# atmega328_dip_board.net
KiCad netlist of a schematic drawn in EAGLE
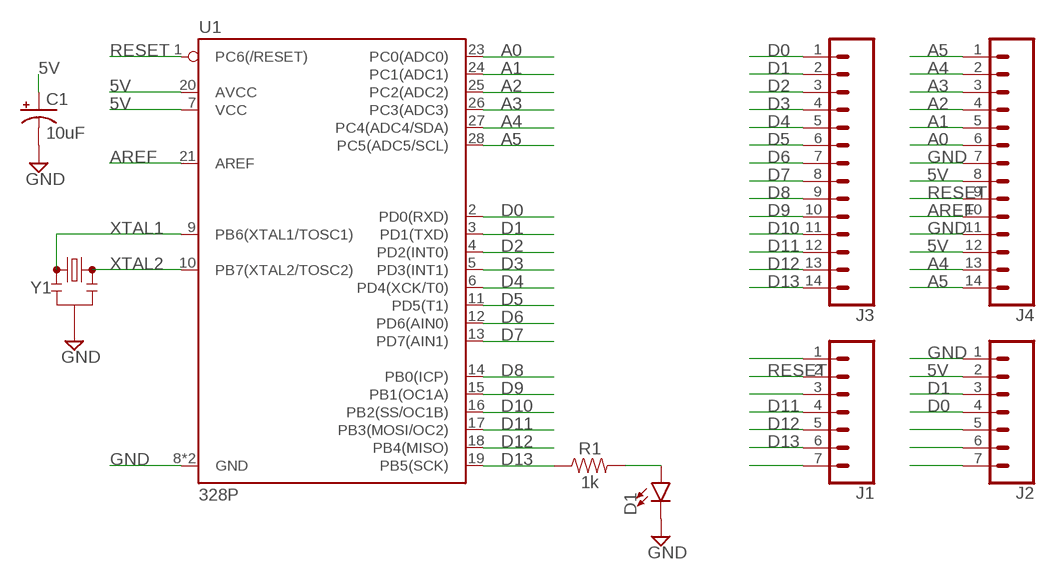
[diagram p0: schematic, sheet 1]

(export (version "E")
  (design (tool "Eeschema 10.0.6"))
  (components
    (comp (ref "C1")
      (value "10uF")
      (footprint "eagle-import:CPOL-RADIAL-2.5MM-5MM")
      (libsource (lib "eagle-import") (part "10UF-POLAR-RADIAL-2.5MM-25V-20%"))
    )
    (comp (ref "D1")
      (value "LED5MM")
      (footprint "eagle-import:LED_5MM")
      (libsource (lib "eagle-import") (part "LED5MM"))
    )
    (comp (ref "J1")
      (value "CONN_07NO_SILK")
      (footprint "eagle-import:1X07_NO_SILK")
      (libsource (lib "eagle-import") (part "CONN_07NO_SILK"))
    )
    (comp (ref "J2")
      (value "CONN_07NO_SILK")
      (footprint "eagle-import:1X07_NO_SILK")
      (libsource (lib "eagle-import") (part "CONN_07NO_SILK"))
    )
    (comp (ref "J3")
      (value "CONN_14NO_SILK")
      (footprint "eagle-import:1X14_NO_SILK")
      (libsource (lib "eagle-import") (part "CONN_14NO_SILK"))
    )
    (comp (ref "J4")
      (value "CONN_14NO_SILK")
      (footprint "eagle-import:1X14_NO_SILK")
      (libsource (lib "eagle-import") (part "CONN_14NO_SILK"))
    )
    (comp (ref "R1")
      (value "1k")
      (footprint "eagle-import:AXIAL-0.3")
      (libsource (lib "eagle-import") (part "1KOHM-HORIZ-1/4W-5%"))
    )
    (comp (ref "U1")
      (value "328P")
      (footprint "eagle-import:DIP28")
      (libsource (lib "eagle-import") (part "ATMEGA328P_PDIP"))
    )
    (comp (ref "Y1")
      (value "RESONATORPTH-7.6X3.8")
      (footprint "eagle-import:RESONATOR-PTH-7.6X3.8")
      (libsource (lib "eagle-import") (part "RESONATORPTH-7.6X3.8"))
    )
  )
  (nets
    (net (code "1") (name "/5V") (class "Default")
      (node (ref "C1") (pin "1") (pinfunction "+_1") (pintype "passive"))
      (node (ref "J2") (pin "2") (pinfunction "2_2") (pintype "passive"))
      (node (ref "J4") (pin "12") (pinfunction "12_12") (pintype "passive"))
      (node (ref "J4") (pin "8") (pinfunction "8_8") (pintype "passive"))
      (node (ref "U1") (pin "20") (pinfunction "AVCC_20") (pintype "bidirectional"))
      (node (ref "U1") (pin "7") (pinfunction "VCC_7") (pintype "bidirectional"))
    )
    (net (code "2") (name "/A0") (class "Default")
      (node (ref "J4") (pin "6") (pinfunction "6_6") (pintype "passive"))
      (node (ref "U1") (pin "23") (pinfunction "PC0(ADC0)_23") (pintype "bidirectional"))
    )
    (net (code "3") (name "/A1") (class "Default")
      (node (ref "J4") (pin "5") (pinfunction "5_5") (pintype "passive"))
      (node (ref "U1") (pin "24") (pinfunction "PC1(ADC1)_24") (pintype "bidirectional"))
    )
    (net (code "4") (name "/A2") (class "Default")
      (node (ref "J4") (pin "4") (pinfunction "4_4") (pintype "passive"))
      (node (ref "U1") (pin "25") (pinfunction "PC2(ADC2)_25") (pintype "bidirectional"))
    )
    (net (code "5") (name "/A3") (class "Default")
      (node (ref "J4") (pin "3") (pinfunction "3_3") (pintype "passive"))
      (node (ref "U1") (pin "26") (pinfunction "PC3(ADC3)_26") (pintype "bidirectional"))
    )
    (net (code "6") (name "/A4") (class "Default")
      (node (ref "J4") (pin "13") (pinfunction "13_13") (pintype "passive"))
      (node (ref "J4") (pin "2") (pinfunction "2_2") (pintype "passive"))
      (node (ref "U1") (pin "27") (pinfunction "PC4(ADC4/SDA)_27") (pintype "bidirectional"))
    )
    (net (code "7") (name "/A5") (class "Default")
      (node (ref "J4") (pin "1") (pinfunction "1_1") (pintype "passive"))
      (node (ref "J4") (pin "14") (pinfunction "14_14") (pintype "passive"))
      (node (ref "U1") (pin "28") (pinfunction "PC5(ADC5/SCL)_28") (pintype "bidirectional"))
    )
    (net (code "8") (name "/AREF") (class "Default")
      (node (ref "J4") (pin "10") (pinfunction "10_10") (pintype "passive"))
      (node (ref "U1") (pin "21") (pinfunction "AREF_21") (pintype "bidirectional"))
    )
    (net (code "9") (name "/D0") (class "Default")
      (node (ref "J2") (pin "4") (pinfunction "4_4") (pintype "passive"))
      (node (ref "J3") (pin "1") (pinfunction "1_1") (pintype "passive"))
      (node (ref "U1") (pin "2") (pinfunction "PD0(RXD)_2") (pintype "bidirectional"))
    )
    (net (code "10") (name "/D1") (class "Default")
      (node (ref "J2") (pin "3") (pinfunction "3_3") (pintype "passive"))
      (node (ref "J3") (pin "2") (pinfunction "2_2") (pintype "passive"))
      (node (ref "U1") (pin "3") (pinfunction "PD1(TXD)_3") (pintype "bidirectional"))
    )
    (net (code "11") (name "/D2") (class "Default")
      (node (ref "J3") (pin "3") (pinfunction "3_3") (pintype "passive"))
      (node (ref "U1") (pin "4") (pinfunction "PD2(INT0)_4") (pintype "bidirectional"))
    )
    (net (code "12") (name "/D3") (class "Default")
      (node (ref "J3") (pin "4") (pinfunction "4_4") (pintype "passive"))
      (node (ref "U1") (pin "5") (pinfunction "PD3(INT1)_5") (pintype "bidirectional"))
    )
    (net (code "13") (name "/D4") (class "Default")
      (node (ref "J3") (pin "5") (pinfunction "5_5") (pintype "passive"))
      (node (ref "U1") (pin "6") (pinfunction "PD4(XCK/T0)_6") (pintype "bidirectional"))
    )
    (net (code "14") (name "/D5") (class "Default")
      (node (ref "J3") (pin "6") (pinfunction "6_6") (pintype "passive"))
      (node (ref "U1") (pin "11") (pinfunction "PD5(T1)_11") (pintype "bidirectional"))
    )
    (net (code "15") (name "/D6") (class "Default")
      (node (ref "J3") (pin "7") (pinfunction "7_7") (pintype "passive"))
      (node (ref "U1") (pin "12") (pinfunction "PD6(AIN0)_12") (pintype "bidirectional"))
    )
    (net (code "16") (name "/D7") (class "Default")
      (node (ref "J3") (pin "8") (pinfunction "8_8") (pintype "passive"))
      (node (ref "U1") (pin "13") (pinfunction "PD7(AIN1)_13") (pintype "bidirectional"))
    )
    (net (code "17") (name "/D8") (class "Default")
      (node (ref "J3") (pin "9") (pinfunction "9_9") (pintype "passive"))
      (node (ref "U1") (pin "14") (pinfunction "PB0(ICP)_14") (pintype "bidirectional"))
    )
    (net (code "18") (name "/D9") (class "Default")
      (node (ref "J3") (pin "10") (pinfunction "10_10") (pintype "passive"))
      (node (ref "U1") (pin "15") (pinfunction "PB1(OC1A)_15") (pintype "bidirectional"))
    )
    (net (code "19") (name "/D10") (class "Default")
      (node (ref "J3") (pin "11") (pinfunction "11_11") (pintype "passive"))
      (node (ref "U1") (pin "16") (pinfunction "PB2(SS/OC1B)_16") (pintype "bidirectional"))
    )
    (net (code "20") (name "/D11") (class "Default")
      (node (ref "J1") (pin "4") (pinfunction "4_4") (pintype "passive"))
      (node (ref "J3") (pin "12") (pinfunction "12_12") (pintype "passive"))
      (node (ref "U1") (pin "17") (pinfunction "PB3(MOSI/OC2)_17") (pintype "bidirectional"))
    )
    (net (code "21") (name "/D12") (class "Default")
      (node (ref "J1") (pin "5") (pinfunction "5_5") (pintype "passive"))
      (node (ref "J3") (pin "13") (pinfunction "13_13") (pintype "passive"))
      (node (ref "U1") (pin "18") (pinfunction "PB4(MISO)_18") (pintype "bidirectional"))
    )
    (net (code "22") (name "/D13") (class "Default")
      (node (ref "J1") (pin "6") (pinfunction "6_6") (pintype "passive"))
      (node (ref "J3") (pin "14") (pinfunction "14_14") (pintype "passive"))
      (node (ref "R1") (pin "P$1") (pinfunction "1_P$1") (pintype "passive"))
      (node (ref "U1") (pin "19") (pinfunction "PB5(SCK)_19") (pintype "bidirectional"))
    )
    (net (code "23") (name "/RESET") (class "Default")
      (node (ref "J1") (pin "2") (pinfunction "2_2") (pintype "passive"))
      (node (ref "J4") (pin "9") (pinfunction "9_9") (pintype "passive"))
      (node (ref "U1") (pin "1") (pinfunction "PC6(/RESET)_1") (pintype "bidirectional"))
    )
    (net (code "24") (name "/XTAL1") (class "Default")
      (node (ref "U1") (pin "9") (pinfunction "PB6(XTAL1/TOSC1)_9") (pintype "bidirectional"))
      (node (ref "Y1") (pin "1") (pinfunction "1_1") (pintype "passive"))
    )
    (net (code "25") (name "/XTAL2") (class "Default")
      (node (ref "U1") (pin "10") (pinfunction "PB7(XTAL2/TOSC2)_10") (pintype "bidirectional"))
      (node (ref "Y1") (pin "3") (pinfunction "3_3") (pintype "passive"))
    )
    (net (code "26") (name "GND") (class "Default")
      (node (ref "C1") (pin "2") (pinfunction "-_2") (pintype "passive"))
      (node (ref "D1") (pin "K") (pinfunction "C_K") (pintype "passive"))
      (node (ref "J2") (pin "1") (pinfunction "1_1") (pintype "passive"))
      (node (ref "J4") (pin "11") (pinfunction "11_11") (pintype "passive"))
      (node (ref "J4") (pin "7") (pinfunction "7_7") (pintype "passive"))
      (node (ref "U1") (pin "22") (pinfunction "GND_22") (pintype "bidirectional"))
      (node (ref "U1") (pin "8") (pinfunction "GND_8") (pintype "bidirectional"))
      (node (ref "Y1") (pin "2") (pinfunction "2_2") (pintype "passive"))
    )
    (net (code "27") (name "Net-(R1-2)") (class "Default")
      (node (ref "D1") (pin "A") (pinfunction "A_A") (pintype "passive"))
      (node (ref "R1") (pin "P$2") (pinfunction "2_P$2") (pintype "passive"))
    )
    (net (code "28") (name "unconnected-(J1-Pad1)") (class "Default")
      (node (ref "J1") (pin "1") (pinfunction "1_1") (pintype "passive"))
    )
    (net (code "29") (name "unconnected-(J1-Pad3)") (class "Default")
      (node (ref "J1") (pin "3") (pinfunction "3_3") (pintype "passive"))
    )
    (net (code "30") (name "unconnected-(J1-Pad7)") (class "Default")
      (node (ref "J1") (pin "7") (pinfunction "7_7") (pintype "passive"))
    )
    (net (code "31") (name "unconnected-(J2-Pad5)") (class "Default")
      (node (ref "J2") (pin "5") (pinfunction "5_5") (pintype "passive"))
    )
    (net (code "32") (name "unconnected-(J2-Pad6)") (class "Default")
      (node (ref "J2") (pin "6") (pinfunction "6_6") (pintype "passive"))
    )
    (net (code "33") (name "unconnected-(J2-Pad7)") (class "Default")
      (node (ref "J2") (pin "7") (pinfunction "7_7") (pintype "passive"))
    )
  )
)
